# Comunicacao.net
KiCad netlist of a schematic drawn in Altium Designer
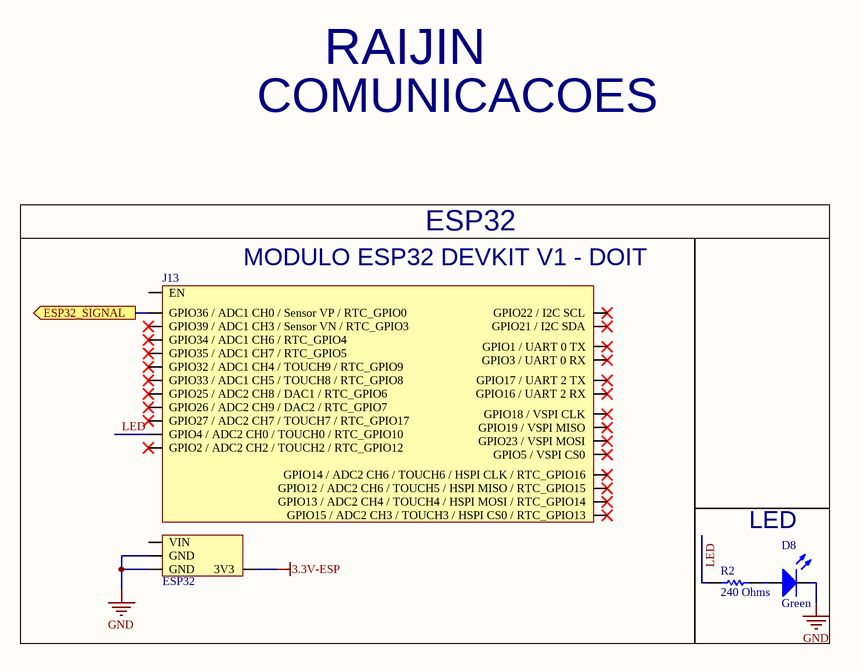
[diagram p0: Comunicacao.SchDoc]

(export (version "E")
  (design (tool "Eeschema 10.0.6"))
  (components
    (comp (ref "D8")
      (value "Green")
      (footprint "LED_0603")
      (description "LED 0.072W GREEN 40MCD 0603")
      (fields
        (field (name "MANUFACTURER") "Wurth Elektronik")
        (field (name "MANUFACTURER PART NUMBER") "150060VS75000")
        (field (name "LIBRARY CONTROL - PERSON THAT CHECKED FOOTPRINT") "Nícolas")
        (field (name "LIBRARY CONTROL - PERSON THAT CHECKED SCHEMATIC") "Nícolas")
        (field (name "LIBRARY CONTROL - PERSON THAT DID THE LAST UPDATE FOOTPRINT") "Marcos")
        (field (name "LIBRARY CONTROL - PERSON THAT DID THE LAST UPDATE SCHEMATIC") "Marcos")
      )
      (libsource (lib "Uai!Tecas") (part "150060VS75000"))
    )
    (comp (ref "J13")
      (value "ESP32")
      (footprint "Modulo ESP32")
      (description "Header Modulo ESP32")
      (fields
        (field (name "LIBRARY CONTROL - CHECKED FOOTPRINT") "Nikaum")
        (field (name "LIBRARY CONTROL - CHECKED SCHEMATIC") "Nikaum")
        (field (name "LIBRARY CONTROL - PERSON THAT DID THE LAST UPDATE SCHEMATIC") "Nikaum")
        (field (name "LIBRARY CONTROL - PERSONT THAT DID THE LAST UPDATE FOOTPRINT") "Nikaum")
      )
      (libsource (lib "Uai!Tecas") (part "Modulo ESP32"))
    )
    (comp (ref "R2")
      (value "240 Ohms")
      (footprint "RESC1608X55N")
      (description "RES SMD 240 OHM 1% 1/10W 0603")
      (fields (field (name "MANUFACTURER") "YAGEO") (field (name "PART NUMBER") "RC0603FR-07240RL"))
      (libsource (lib "Uai!Tecas") (part "RC0603FR-07240RL"))
    )
  )
  (nets
    (net (code "1") (name "/ESP32_SIGNAL") (class "Default")
      (node (ref "J13") (pin "PIN2") (pinfunction "GPIO36_/_ADC1_CH0_/_Sensor_VP_/_RTC_GPIO0_PIN2") (pintype "passive"))
    )
    (net (code "2") (name "/LED") (class "Default")
      (node (ref "J13") (pin "PIN26") (pinfunction "GPIO4_/_ADC2_CH0_/_TOUCH0_/_RTC_GPIO10_PIN26") (pintype "passive"))
      (node (ref "R2") (pin "1") (pinfunction "1_1") (pintype "passive"))
    )
    (net (code "3") (name "3.3V-ESP") (class "Default")
      (node (ref "J13") (pin "3V3") (pinfunction "3V3_3V3") (pintype "passive"))
    )
    (net (code "4") (name "GND") (class "Default")
      (node (ref "D8") (pin "C") (pinfunction "C_C") (pintype "passive"))
      (node (ref "J13") (pin "GND") (pinfunction "GND_GND") (pintype "passive"))
    )
    (net (code "5") (name "Net-(D8-PadA)") (class "Default")
      (node (ref "D8") (pin "A") (pinfunction "A_A") (pintype "passive"))
      (node (ref "R2") (pin "2") (pinfunction "2_2") (pintype "passive"))
    )
    (net (code "6") (name "unconnected-(J13-GPIO1_{slash}_UART_0_TX-PadPIN18)") (class "Default")
      (node (ref "J13") (pin "PIN18") (pinfunction "GPIO1_/_UART_0_TX_PIN18") (pintype "passive+no_connect"))
    )
    (net (code "7") (name "unconnected-(J13-GPIO2_{slash}_ADC2_CH2_{slash}_TOUCH2_{slash}_RTC_GPIO12-PadPIN27)") (class "Default")
      (node (ref "J13") (pin "PIN27") (pinfunction "GPIO2_/_ADC2_CH2_/_TOUCH2_/_RTC_GPIO12_PIN27") (pintype "passive+no_connect"))
    )
    (net (code "8") (name "unconnected-(J13-GPIO3_{slash}_UART_0_RX-PadPIN19)") (class "Default")
      (node (ref "J13") (pin "PIN19") (pinfunction "GPIO3_/_UART_0_RX_PIN19") (pintype "passive+no_connect"))
    )
    (net (code "9") (name "unconnected-(J13-GPIO5_{slash}_VSPI_CS0-PadPIN23)") (class "Default")
      (node (ref "J13") (pin "PIN23") (pinfunction "GPIO5_/_VSPI_CS0_PIN23") (pintype "passive+no_connect"))
    )
    (net (code "10") (name "unconnected-(J13-GPIO12_{slash}_ADC2_CH6_{slash}_TOUCH5_{slash}_HSPI_MISO_{slash}_RTC_GPIO15-PadPIN12)") (class "Default")
      (node (ref "J13") (pin "PIN12") (pinfunction "GPIO12_/_ADC2_CH6_/_TOUCH5_/_HSPI_MISO_/_RTC_GPIO15_PIN12") (pintype "passive+no_connect"))
    )
    (net (code "11") (name "unconnected-(J13-GPIO13_{slash}_ADC2_CH4_{slash}_TOUCH4_{slash}_HSPI_MOSI_{slash}_RTC_GPIO14-PadPIN13)") (class "Default")
      (node (ref "J13") (pin "PIN13") (pinfunction "GPIO13_/_ADC2_CH4_/_TOUCH4_/_HSPI_MOSI_/_RTC_GPIO14_PIN13") (pintype "passive+no_connect"))
    )
    (net (code "12") (name "unconnected-(J13-GPIO14_{slash}_ADC2_CH6_{slash}_TOUCH6_{slash}_HSPI_CLK_{slash}_RTC_GPIO16-PadPIN11)") (class "Default")
      (node (ref "J13") (pin "PIN11") (pinfunction "GPIO14_/_ADC2_CH6_/_TOUCH6_/_HSPI_CLK_/_RTC_GPIO16_PIN11") (pintype "passive+no_connect"))
    )
    (net (code "13") (name "unconnected-(J13-GPIO15_{slash}_ADC2_CH3_{slash}_TOUCH3_{slash}_HSPI_CS0_{slash}_RTC_GPIO13-PadPIN28)") (class "Default")
      (node (ref "J13") (pin "PIN28") (pinfunction "GPIO15_/_ADC2_CH3_/_TOUCH3_/_HSPI_CS0_/_RTC_GPIO13_PIN28") (pintype "passive+no_connect"))
    )
    (net (code "14") (name "unconnected-(J13-GPIO16_{slash}_UART_2_RX-PadPIN25)") (class "Default")
      (node (ref "J13") (pin "PIN25") (pinfunction "GPIO16_/_UART_2_RX_PIN25") (pintype "passive+no_connect"))
    )
    (net (code "15") (name "unconnected-(J13-GPIO17_{slash}_UART_2_TX-PadPIN24)") (class "Default")
      (node (ref "J13") (pin "PIN24") (pinfunction "GPIO17_/_UART_2_TX_PIN24") (pintype "passive+no_connect"))
    )
    (net (code "16") (name "unconnected-(J13-GPIO18_{slash}_VSPI_CLK-PadPIN22)") (class "Default")
      (node (ref "J13") (pin "PIN22") (pinfunction "GPIO18_/_VSPI_CLK_PIN22") (pintype "passive+no_connect"))
    )
    (net (code "17") (name "unconnected-(J13-GPIO19_{slash}_VSPI_MISO-PadPIN21)") (class "Default")
      (node (ref "J13") (pin "PIN21") (pinfunction "GPIO19_/_VSPI_MISO_PIN21") (pintype "passive+no_connect"))
    )
    (net (code "18") (name "unconnected-(J13-GPIO21_{slash}_I2C_SDA-PadPIN20)") (class "Default")
      (node (ref "J13") (pin "PIN20") (pinfunction "GPIO21_/_I2C_SDA_PIN20") (pintype "passive+no_connect"))
    )
    (net (code "19") (name "unconnected-(J13-GPIO22_{slash}_I2C_SCL-PadPIN17)") (class "Default")
      (node (ref "J13") (pin "PIN17") (pinfunction "GPIO22_/_I2C_SCL_PIN17") (pintype "passive+no_connect"))
    )
    (net (code "20") (name "unconnected-(J13-GPIO23_{slash}_VSPI_MOSI-PadPIN16)") (class "Default")
      (node (ref "J13") (pin "PIN16") (pinfunction "GPIO23_/_VSPI_MOSI_PIN16") (pintype "passive+no_connect"))
    )
    (net (code "21") (name "unconnected-(J13-GPIO25_{slash}_ADC2_CH8_{slash}_DAC1_{slash}_RTC_GPIO6-PadPIN8)") (class "Default")
      (node (ref "J13") (pin "PIN8") (pinfunction "GPIO25_/_ADC2_CH8_/_DAC1_/_RTC_GPIO6_PIN8") (pintype "passive+no_connect"))
    )
    (net (code "22") (name "unconnected-(J13-GPIO26_{slash}_ADC2_CH9_{slash}_DAC2_{slash}_RTC_GPIO7-PadPIN9)") (class "Default")
      (node (ref "J13") (pin "PIN9") (pinfunction "GPIO26_/_ADC2_CH9_/_DAC2_/_RTC_GPIO7_PIN9") (pintype "passive+no_connect"))
    )
    (net (code "23") (name "unconnected-(J13-GPIO27_{slash}_ADC2_CH7_{slash}_TOUCH7_{slash}_RTC_GPIO17-PadPIN10)") (class "Default")
      (node (ref "J13") (pin "PIN10") (pinfunction "GPIO27_/_ADC2_CH7_/_TOUCH7_/_RTC_GPIO17_PIN10") (pintype "passive+no_connect"))
    )
    (net (code "24") (name "unconnected-(J13-GPIO32_{slash}_ADC1_CH4_{slash}_TOUCH9_{slash}_RTC_GPIO9-PadPIN6)") (class "Default")
      (node (ref "J13") (pin "PIN6") (pinfunction "GPIO32_/_ADC1_CH4_/_TOUCH9_/_RTC_GPIO9_PIN6") (pintype "passive+no_connect"))
    )
    (net (code "25") (name "unconnected-(J13-GPIO33_{slash}_ADC1_CH5_{slash}_TOUCH8_{slash}_RTC_GPIO8-PadPIN7)") (class "Default")
      (node (ref "J13") (pin "PIN7") (pinfunction "GPIO33_/_ADC1_CH5_/_TOUCH8_/_RTC_GPIO8_PIN7") (pintype "passive+no_connect"))
    )
    (net (code "26") (name "unconnected-(J13-GPIO34_{slash}_ADC1_CH6_{slash}_RTC_GPIO4-PadPIN4)") (class "Default")
      (node (ref "J13") (pin "PIN4") (pinfunction "GPIO34_/_ADC1_CH6_/_RTC_GPIO4_PIN4") (pintype "passive+no_connect"))
    )
    (net (code "27") (name "unconnected-(J13-GPIO35_{slash}_ADC1_CH7_{slash}_RTC_GPIO5-PadPIN5)") (class "Default")
      (node (ref "J13") (pin "PIN5") (pinfunction "GPIO35_/_ADC1_CH7_/_RTC_GPIO5_PIN5") (pintype "passive+no_connect"))
    )
    (net (code "28") (name "unconnected-(J13-GPIO39_{slash}_ADC1_CH3_{slash}_Sensor_VN_{slash}_RTC_GPIO3-PadPIN3)") (class "Default")
      (node (ref "J13") (pin "PIN3") (pinfunction "GPIO39_/_ADC1_CH3_/_Sensor_VN_/_RTC_GPIO3_PIN3") (pintype "passive+no_connect"))
    )
    (net (code "29") (name "unconnected-(J13-PadEN)") (class "Default")
      (node (ref "J13") (pin "EN") (pinfunction "EN_EN") (pintype "passive"))
    )
    (net (code "30") (name "unconnected-(J13-PadVIN)") (class "Default")
      (node (ref "J13") (pin "VIN") (pinfunction "VIN_VIN") (pintype "passive"))
    )
  )
)
